# SCH.net
KiCad netlist of a schematic drawn in EasyEDA
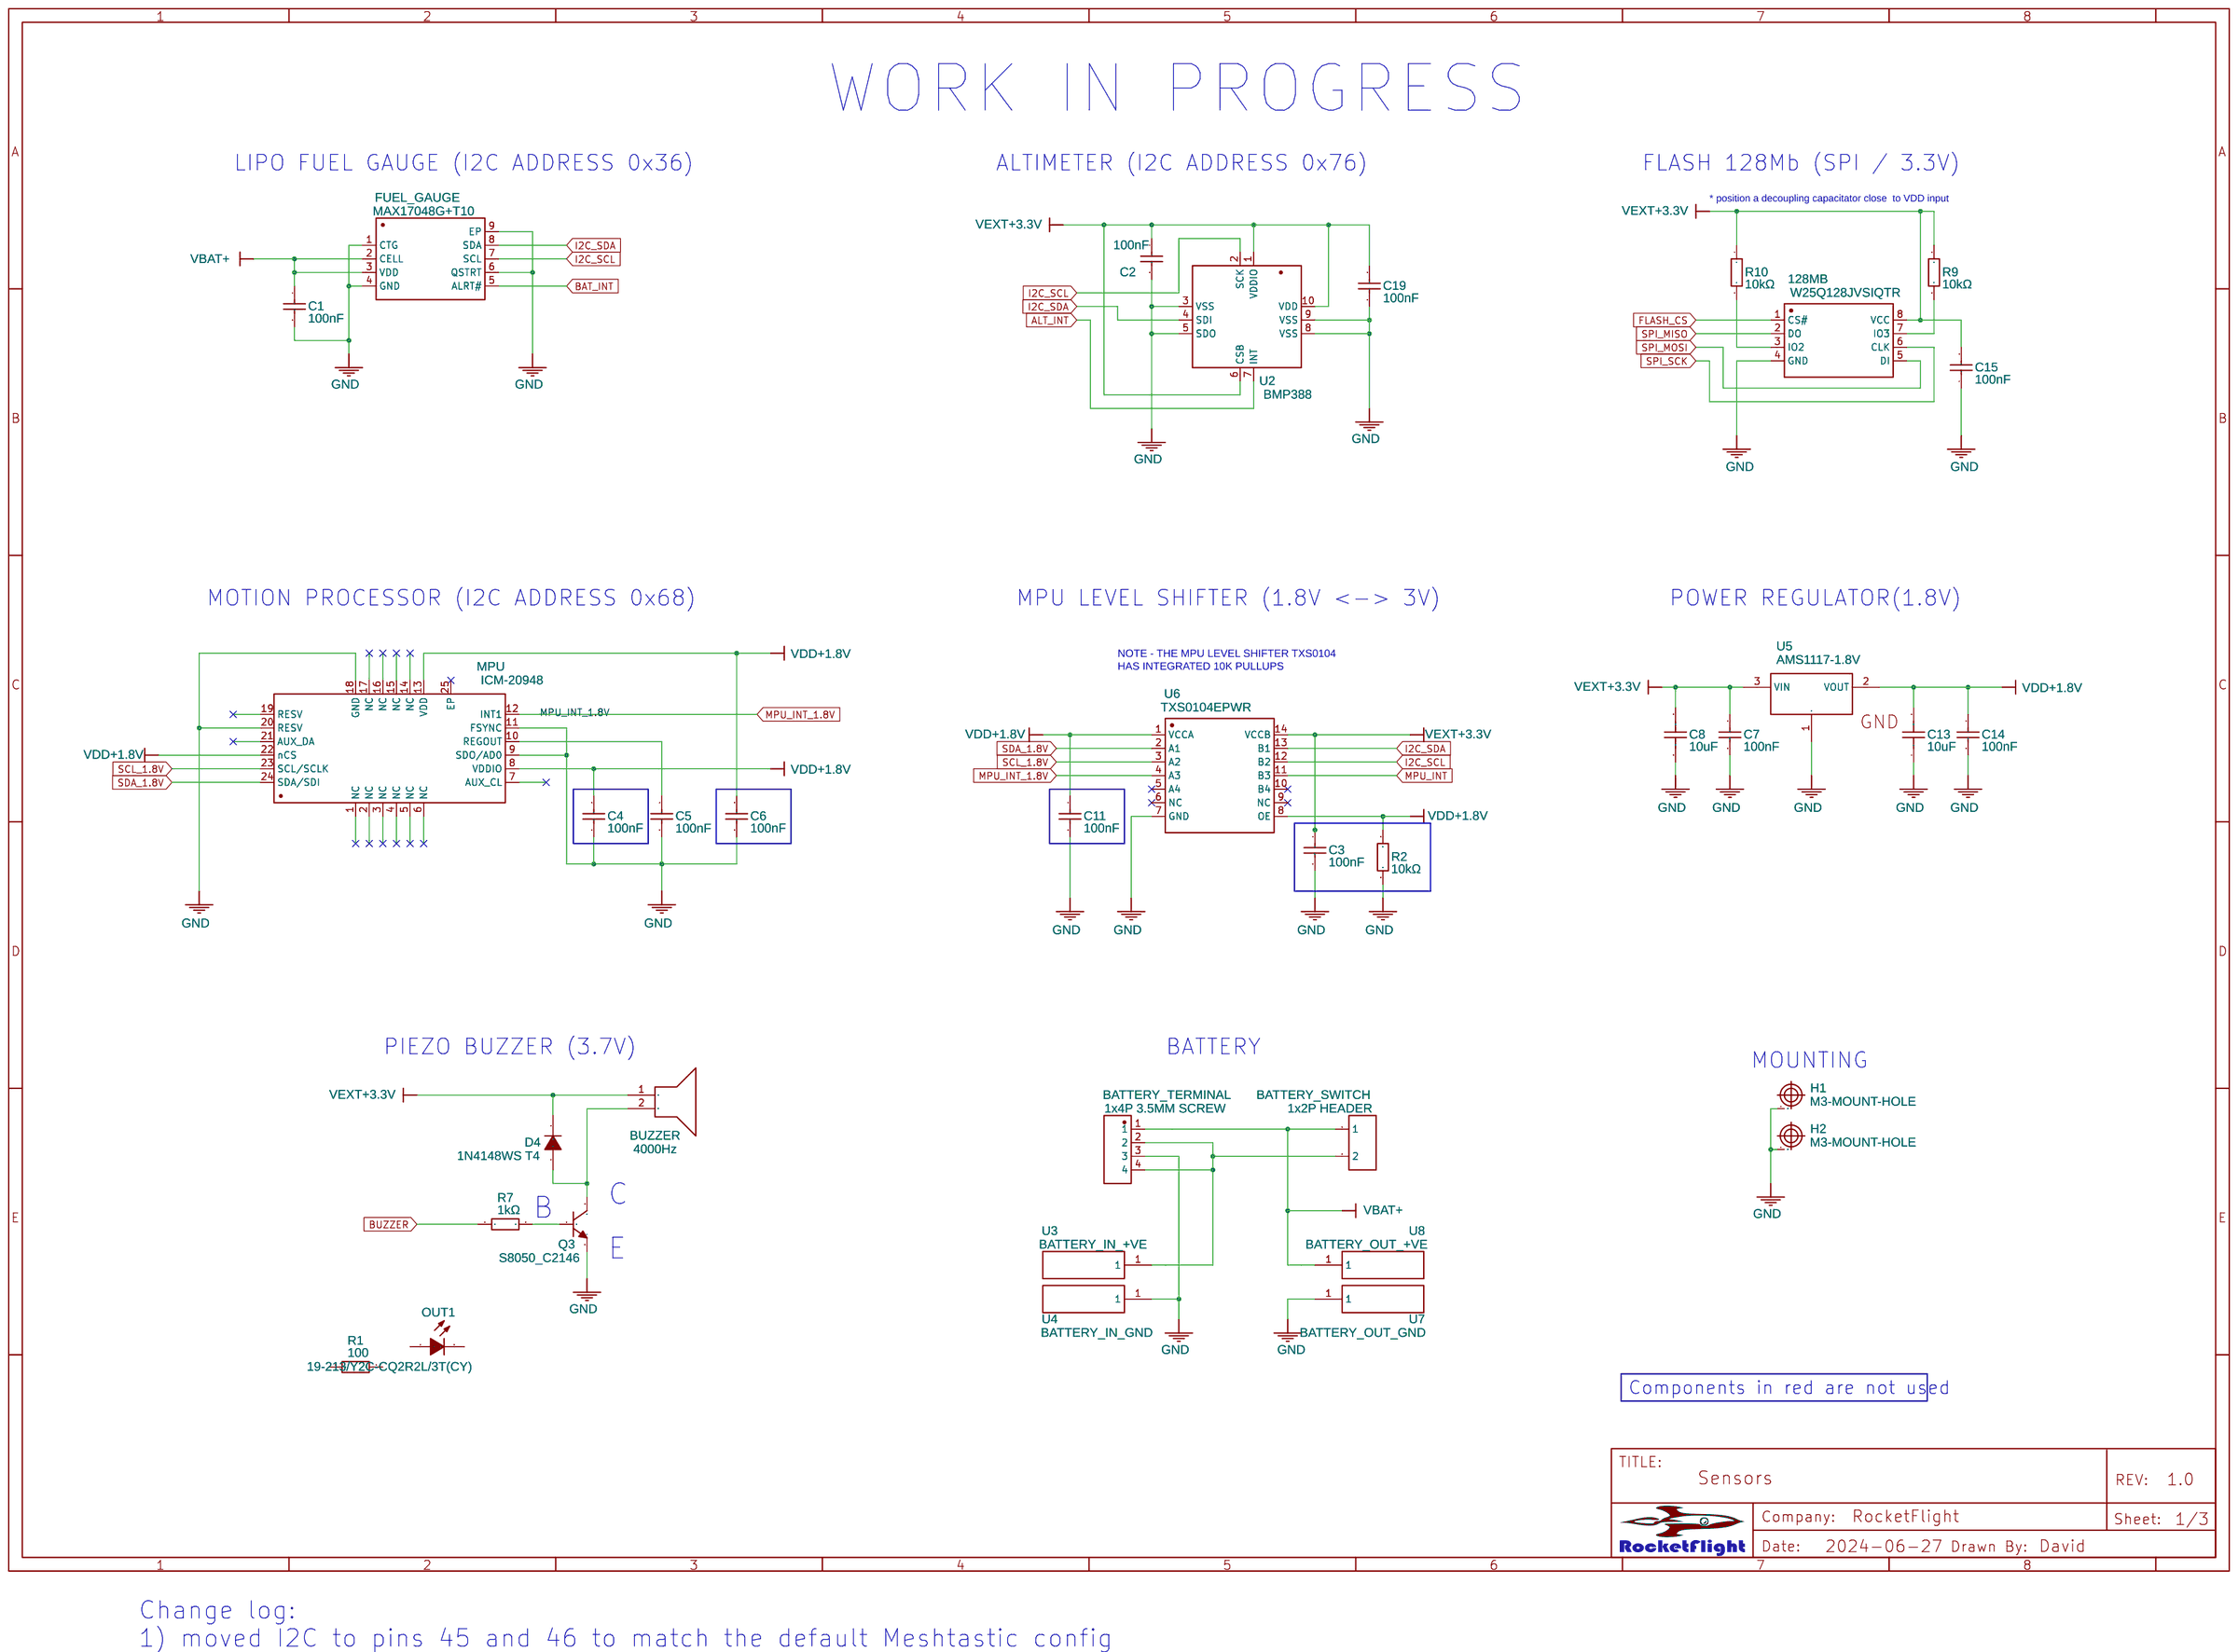
[diagram p0: Sensors]
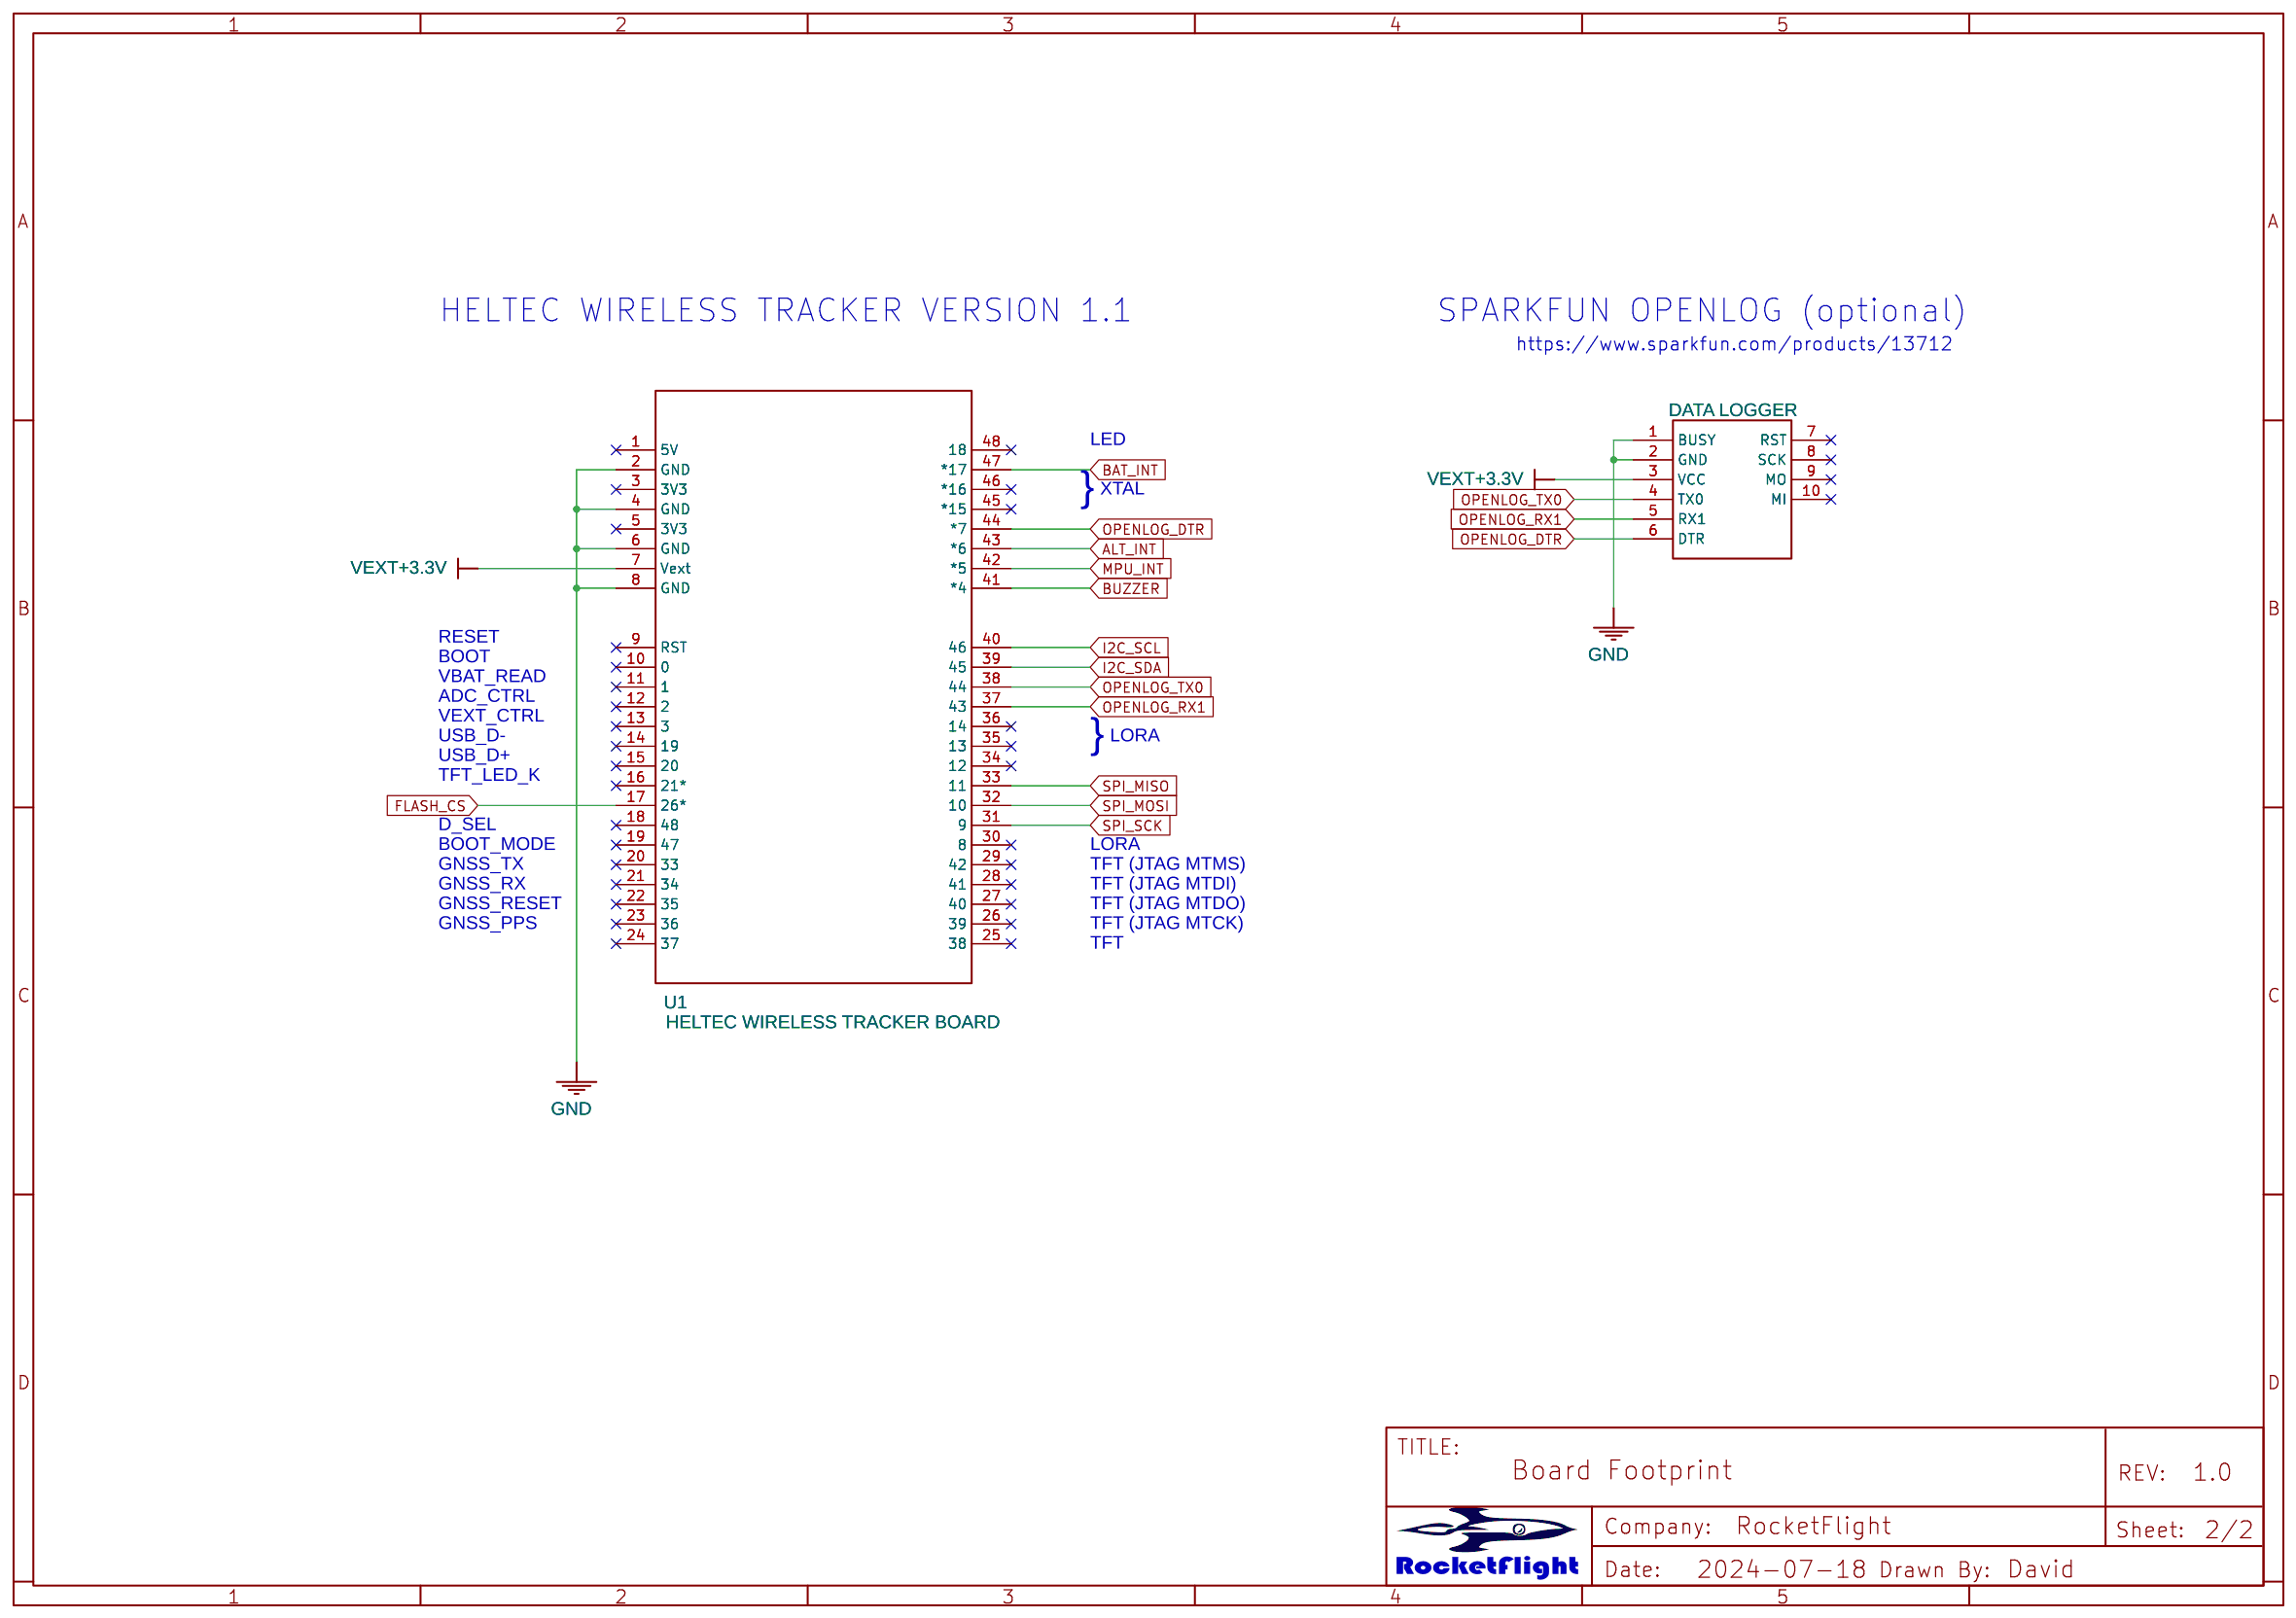
[diagram p1: Board]

(export (version "E")
  (design (tool "Eeschema 10.0.6"))
  (components
    (comp (ref "128MB")
      (value "W25Q128JVSIQTR")
      (fields (field (name "Manufacturer Part") "W25Q128JVSIQ") (field (name "Manufacturer") "WINBOND(华邦)"))
      (libsource (lib "") (part "W25Q128JVSIQTR"))
    )
    (comp (ref "BATTERY_SWITCH")
      (value "1x2P HEADER")
      (fields (field (name "Manufacturer Part") "826629-2") (field (name "Manufacturer") "TE Connectivity"))
      (libsource (lib "") (part "HDR-M-2.54_1X2_ROUND"))
    )
    (comp (ref "BATTERY_TERMINAL")
      (value "1x4P 3.5MM SCREW")
      (fields (field (name "Manufacturer Part") "XY350V-3.5-4P") (field (name "Manufacturer") "--"))
      (libsource (lib "") (part "XY350V-3.5-4P"))
    )
    (comp (ref "BUZZER")
      (value "4000Hz")
      (fields (field (name "Manufacturer Part") "FUET-9018") (field (name "Manufacturer") "FUET(福声科技)"))
      (libsource (lib "") (part "FST-9018 COPY"))
    )
    (comp (ref "C1")
      (value "100nF")
      (fields
        (field (name "Manufacturer Part") "CL05B104KO5NNNC")
        (field (name "Manufacturer") "SAMSUNG(三星)")
      )
      (libsource (lib "") (part "CL05B104KO5NNNC"))
    )
    (comp (ref "C2")
      (value "100nF")
      (fields
        (field (name "Manufacturer Part") "CL05B104KO5NNNC")
        (field (name "Manufacturer") "SAMSUNG(三星)")
      )
      (libsource (lib "") (part "CL05B104KO5NNNC"))
    )
    (comp (ref "C3")
      (value "100nF")
      (fields
        (field (name "Manufacturer Part") "CL05B104KO5NNNC")
        (field (name "Manufacturer") "SAMSUNG(三星)")
      )
      (libsource (lib "") (part "CL05B104KO5NNNC"))
    )
    (comp (ref "C4")
      (value "100nF")
      (fields
        (field (name "Manufacturer Part") "CL05B104KO5NNNC")
        (field (name "Manufacturer") "SAMSUNG(三星)")
      )
      (libsource (lib "") (part "CL05B104KO5NNNC_1"))
    )
    (comp (ref "C5")
      (value "100nF")
      (fields
        (field (name "Manufacturer Part") "CL05B104KO5NNNC")
        (field (name "Manufacturer") "SAMSUNG(三星)")
      )
      (libsource (lib "") (part "CL05B104KO5NNNC"))
    )
    (comp (ref "C6")
      (value "100nF")
      (fields
        (field (name "Manufacturer Part") "CL05B104KO5NNNC")
        (field (name "Manufacturer") "SAMSUNG(三星)")
      )
      (libsource (lib "") (part "CL05B104KO5NNNC_1"))
    )
    (comp (ref "C7")
      (value "100nF")
      (fields
        (field (name "Manufacturer Part") "CL05B104KO5NNNC")
        (field (name "Manufacturer") "SAMSUNG(三星)")
      )
      (libsource (lib "") (part "CL05B104KO5NNNC_1"))
    )
    (comp (ref "C8")
      (value "10uF")
      (fields
        (field (name "Manufacturer Part") "CL10A106MA8NRNC")
        (field (name "Manufacturer") "SAMSUNG(三星)")
      )
      (libsource (lib "") (part "CL10A106MA8NRNC"))
    )
    (comp (ref "C11")
      (value "100nF")
      (fields
        (field (name "Manufacturer Part") "CL05B104KO5NNNC")
        (field (name "Manufacturer") "SAMSUNG(三星)")
      )
      (libsource (lib "") (part "CL05B104KO5NNNC"))
    )
    (comp (ref "C13")
      (value "10uF")
      (fields
        (field (name "Manufacturer Part") "CL10A106MA8NRNC")
        (field (name "Manufacturer") "SAMSUNG(三星)")
      )
      (libsource (lib "") (part "CL10A106MA8NRNC"))
    )
    (comp (ref "C14")
      (value "100nF")
      (fields
        (field (name "Manufacturer Part") "CL05B104KO5NNNC")
        (field (name "Manufacturer") "SAMSUNG(三星)")
      )
      (libsource (lib "") (part "CL05B104KO5NNNC_1"))
    )
    (comp (ref "C15")
      (value "100nF")
      (fields
        (field (name "Manufacturer Part") "CL05B104KO5NNNC")
        (field (name "Manufacturer") "SAMSUNG(三星)")
      )
      (libsource (lib "") (part "CL05B104KO5NNNC_1"))
    )
    (comp (ref "C19")
      (value "100nF")
      (fields
        (field (name "Manufacturer Part") "CL05B104KO5NNNC")
        (field (name "Manufacturer") "SAMSUNG(三星)")
      )
      (libsource (lib "") (part "CL05B104KO5NNNC"))
    )
    (comp (ref "D4")
      (value "1N4148WS T4")
      (fields (field (name "Manufacturer Part") "1N4148WS") (field (name "Manufacturer") "CJ(江苏长电/长晶)"))
      (libsource (lib "") (part "1N4148WS T4"))
    )
    (comp (ref "FUEL_GAUGE")
      (value "MAX17048G+T10")
      (fields (field (name "Manufacturer") "ADI(亚德诺)/MAXIM(美信)"))
      (libsource (lib "") (part "MAX17048G+T10"))
    )
    (comp (ref "H1") (value "M3-MOUNT-HOLE") (libsource (lib "") (part "M3-MOUNT-HOLE")))
    (comp (ref "H2") (value "M3-MOUNT-HOLE") (libsource (lib "") (part "M3-MOUNT-HOLE")))
    (comp (ref "MPU")
      (value "ICM-20948")
      (fields (field (name "Manufacturer") "TDK InvenSense(应美盛)"))
      (libsource (lib "") (part "ICM-20948"))
    )
    (comp (ref "OUT1")
      (value "19-213/Y2C-CQ2R2L/3T(CY)")
      (fields (field (name "Manufacturer") "EVERLIGHT"))
      (libsource (lib "") (part "19-213/Y2C-CQ2R2L/3T(CY)"))
    )
    (comp (ref "Q3")
      (value "S8050_C2146")
      (fields (field (name "Manufacturer Part") "S8050 J3Y") (field (name "Manufacturer") "CJ(江苏长电/长晶)"))
      (libsource (lib "") (part "S8050_C2146"))
    )
    (comp (ref "R1")
      (value "100")
      (fields (field (name "Manufacturer Part") "0603WAF1000T5E") (field (name "Manufacturer") "UniOhm"))
      (libsource (lib "") (part "0603WAF1000T5E"))
    )
    (comp (ref "R2")
      (value "10kΩ")
      (fields
        (field (name "Manufacturer Part") "0402WGF1002TCE")
        (field (name "Manufacturer") "UNI-ROYAL(厚声)")
      )
      (libsource (lib "") (part "0402WGF1002TCE_1"))
    )
    (comp (ref "R7")
      (value "1kΩ")
      (fields
        (field (name "Manufacturer Part") "0603WAF1001T5E")
        (field (name "Manufacturer") "UNI-ROYAL(厚声)")
      )
      (libsource (lib "") (part "0603WAF1001T5E"))
    )
    (comp (ref "R9")
      (value "10kΩ")
      (fields
        (field (name "Manufacturer Part") "0402WGF1002TCE")
        (field (name "Manufacturer") "UNI-ROYAL(厚声)")
      )
      (libsource (lib "") (part "0402WGF1002TCE"))
    )
    (comp (ref "R10")
      (value "10kΩ")
      (fields
        (field (name "Manufacturer Part") "0402WGF1002TCE")
        (field (name "Manufacturer") "UNI-ROYAL(厚声)")
      )
      (libsource (lib "") (part "0402WGF1002TCE"))
    )
    (comp (ref "U2")
      (value "BMP388")
      (fields (field (name "Manufacturer") "Bosch(博世)"))
      (libsource (lib "") (part "BMP388"))
    )
    (comp (ref "U3")
      (value "BATTERY_IN_+VE")
      (fields (field (name "Manufacturer Part") "PAD_5.84mm×1.54mm×0.8mm"))
      (libsource (lib "") (part "MySolderPad1.5x2.5mm"))
    )
    (comp (ref "U4")
      (value "BATTERY_IN_GND")
      (fields (field (name "Manufacturer Part") "PAD_5.84mm×1.54mm×0.8mm"))
      (libsource (lib "") (part "MySolderPad1.5x2.5mm"))
    )
    (comp (ref "U5")
      (value "AMS1117-1.8V")
      (fields (field (name "Manufacturer") "MSKSEMI(美森科)"))
      (libsource (lib "") (part "AMS1117-1.8V"))
    )
    (comp (ref "U6")
      (value "TXS0104EPWR")
      (fields (field (name "Manufacturer") "TI(德州仪器)"))
      (libsource (lib "") (part "TXS0104EPWR"))
    )
    (comp (ref "U7")
      (value "BATTERY_OUT_GND")
      (fields (field (name "Manufacturer Part") "PAD_5.84mm×1.54mm×0.8mm"))
      (libsource (lib "") (part "MySolderPad1.5x2.5mm_1"))
    )
    (comp (ref "U8")
      (value "BATTERY_OUT_+VE")
      (fields (field (name "Manufacturer Part") "PAD_5.84mm×1.54mm×0.8mm"))
      (libsource (lib "") (part "MySolderPad1.5x2.5mm_1"))
    )
    (comp (ref "BUSY")
      (value "DATA LOGGER")
      (fields (field (name "Manufacturer Part") "Sparkfun"))
      (libsource (lib "") (part "DATA LOGGER_RN_OPENLOG COPY"))
    )
    (comp (ref "U1")
      (value "HELTEC WIRELESS TRACKER BOARD")
      (libsource (lib "") (part "HELTEC WIRELESS TRACKER BOARD"))
    )
  )
  (nets
    (net (code "1") (name "ALT_INT") (class "Default")
      (node (ref "U1") (pin "43") (pinfunction "*6_43") (pintype "unspecified"))
      (node (ref "U2") (pin "7") (pinfunction "INT_7") (pintype "unspecified"))
    )
    (net (code "2") (name "BAT_INT") (class "Default")
      (node (ref "FUEL_GAUGE") (pin "5") (pinfunction "ALRT#_5") (pintype "unspecified"))
      (node (ref "U1") (pin "47") (pinfunction "*17_47") (pintype "unspecified"))
    )
    (net (code "3") (name "BUZZER") (class "Default")
      (node (ref "R7") (pin "1") (pinfunction "1_1") (pintype "input"))
      (node (ref "U1") (pin "41") (pinfunction "*4_41") (pintype "unspecified"))
    )
    (net (code "4") (name "FLASH_CS") (class "Default")
      (node (ref "128MB") (pin "1") (pinfunction "CS#_1") (pintype "unspecified"))
      (node (ref "U1") (pin "17") (pinfunction "26*_17") (pintype "unspecified"))
    )
    (net (code "5") (name "GND") (class "Default")
      (node (ref "128MB") (pin "4") (pinfunction "GND_4") (pintype "unspecified"))
      (node (ref "BATTERY_TERMINAL") (pin "3") (pinfunction "3_3") (pintype "unspecified"))
      (node (ref "BUSY") (pin "1") (pinfunction "BUSY_1") (pintype "unspecified"))
      (node (ref "BUSY") (pin "2") (pinfunction "GND_2") (pintype "unspecified"))
      (node (ref "C1") (pin "2") (pinfunction "2_2") (pintype "input"))
      (node (ref "C11") (pin "2") (pinfunction "2_2") (pintype "input"))
      (node (ref "C13") (pin "1") (pinfunction "1_1") (pintype "unspecified"))
      (node (ref "C14") (pin "1") (pinfunction "1_1") (pintype "input"))
      (node (ref "C15") (pin "1") (pinfunction "1_1") (pintype "input"))
      (node (ref "C19") (pin "2") (pinfunction "2_2") (pintype "input"))
      (node (ref "C2") (pin "2") (pinfunction "2_2") (pintype "input"))
      (node (ref "C3") (pin "2") (pinfunction "2_2") (pintype "input"))
      (node (ref "C4") (pin "1") (pinfunction "1_1") (pintype "input"))
      (node (ref "C5") (pin "2") (pinfunction "2_2") (pintype "input"))
      (node (ref "C6") (pin "1") (pinfunction "1_1") (pintype "input"))
      (node (ref "C7") (pin "1") (pinfunction "1_1") (pintype "input"))
      (node (ref "C8") (pin "1") (pinfunction "1_1") (pintype "unspecified"))
      (node (ref "FUEL_GAUGE") (pin "1") (pinfunction "CTG_1") (pintype "unspecified"))
      (node (ref "FUEL_GAUGE") (pin "4") (pinfunction "GND_4") (pintype "unspecified"))
      (node (ref "FUEL_GAUGE") (pin "6") (pinfunction "QSTRT_6") (pintype "unspecified"))
      (node (ref "FUEL_GAUGE") (pin "9") (pinfunction "EP_9") (pintype "unspecified"))
      (node (ref "H1") (pin "1") (pinfunction "GND_1") (pintype "passive"))
      (node (ref "H2") (pin "1") (pinfunction "GND_1") (pintype "passive"))
      (node (ref "MPU") (pin "11") (pinfunction "FSYNC_11") (pintype "unspecified"))
      (node (ref "MPU") (pin "18") (pinfunction "GND_18") (pintype "unspecified"))
      (node (ref "MPU") (pin "20") (pinfunction "RESV_20") (pintype "unspecified"))
      (node (ref "MPU") (pin "9") (pinfunction "SDO/AD0_9") (pintype "unspecified"))
      (node (ref "Q3") (pin "2") (pinfunction "E_2") (pintype "unspecified"))
      (node (ref "R2") (pin "1") (pinfunction "1_1") (pintype "input"))
      (node (ref "U1") (pin "2") (pinfunction "GND_2") (pintype "unspecified"))
      (node (ref "U1") (pin "4") (pinfunction "GND_4") (pintype "unspecified"))
      (node (ref "U1") (pin "6") (pinfunction "GND_6") (pintype "unspecified"))
      (node (ref "U1") (pin "8") (pinfunction "GND_8") (pintype "unspecified"))
      (node (ref "U2") (pin "3") (pinfunction "VSS_3") (pintype "unspecified"))
      (node (ref "U2") (pin "5") (pinfunction "SDO_5") (pintype "unspecified"))
      (node (ref "U2") (pin "8") (pinfunction "VSS_8") (pintype "unspecified"))
      (node (ref "U2") (pin "9") (pinfunction "VSS_9") (pintype "unspecified"))
      (node (ref "U4") (pin "1") (pinfunction "1_1") (pintype "unspecified"))
      (node (ref "U5") (pin "1") (pinfunction "GND_1") (pintype "passive"))
      (node (ref "U6") (pin "7") (pinfunction "GND_7") (pintype "unspecified"))
      (node (ref "U7") (pin "1") (pinfunction "1_1") (pintype "unspecified"))
    )
    (net (code "6") (name "I2C_SCL") (class "Default")
      (node (ref "FUEL_GAUGE") (pin "7") (pinfunction "SCL_7") (pintype "unspecified"))
      (node (ref "U1") (pin "40") (pinfunction "46_40") (pintype "unspecified"))
      (node (ref "U2") (pin "2") (pinfunction "SCK_2") (pintype "unspecified"))
      (node (ref "U6") (pin "12") (pinfunction "B2_12") (pintype "unspecified"))
    )
    (net (code "7") (name "I2C_SDA") (class "Default")
      (node (ref "FUEL_GAUGE") (pin "8") (pinfunction "SDA_8") (pintype "unspecified"))
      (node (ref "U1") (pin "39") (pinfunction "45_39") (pintype "unspecified"))
      (node (ref "U2") (pin "4") (pinfunction "SDI_4") (pintype "unspecified"))
      (node (ref "U6") (pin "13") (pinfunction "B1_13") (pintype "unspecified"))
    )
    (net (code "8") (name "MPU_INT") (class "Default")
      (node (ref "U1") (pin "42") (pinfunction "*5_42") (pintype "unspecified"))
      (node (ref "U6") (pin "11") (pinfunction "B3_11") (pintype "unspecified"))
    )
    (net (code "9") (name "MPU_INT_1.8V") (class "Default")
      (node (ref "MPU") (pin "12") (pinfunction "INT1_12") (pintype "unspecified"))
      (node (ref "U6") (pin "4") (pinfunction "A3_4") (pintype "unspecified"))
    )
    (net (code "10") (name "Net-(128MB-IO2)") (class "Default")
      (node (ref "128MB") (pin "3") (pinfunction "IO2_3") (pintype "unspecified"))
      (node (ref "R10") (pin "2") (pinfunction "2_2") (pintype "input"))
    )
    (net (code "11") (name "Net-(128MB-IO3)") (class "Default")
      (node (ref "128MB") (pin "7") (pinfunction "IO3_7") (pintype "unspecified"))
      (node (ref "R9") (pin "2") (pinfunction "2_2") (pintype "input"))
    )
    (net (code "12") (name "Net-(BATTERY_SWITCH-Pad2)") (class "Default")
      (node (ref "BATTERY_SWITCH") (pin "2") (pinfunction "2_2") (pintype "unspecified"))
      (node (ref "BATTERY_TERMINAL") (pin "2") (pinfunction "2_2") (pintype "unspecified"))
      (node (ref "BATTERY_TERMINAL") (pin "4") (pinfunction "4_4") (pintype "unspecified"))
      (node (ref "U3") (pin "1") (pinfunction "1_1") (pintype "unspecified"))
    )
    (net (code "13") (name "Net-(D4-A)") (class "Default")
      (node (ref "BUZZER") (pin "2") (pinfunction "2_2") (pintype "unspecified"))
      (node (ref "D4") (pin "2") (pinfunction "A_2") (pintype "unspecified"))
      (node (ref "Q3") (pin "3") (pinfunction "C_3") (pintype "unspecified"))
    )
    (net (code "14") (name "Net-(MPU-REGOUT)") (class "Default")
      (node (ref "C5") (pin "1") (pinfunction "1_1") (pintype "input"))
      (node (ref "MPU") (pin "10") (pinfunction "REGOUT_10") (pintype "unspecified"))
    )
    (net (code "15") (name "Net-(Q3-B)") (class "Default")
      (node (ref "Q3") (pin "1") (pinfunction "B_1") (pintype "unspecified"))
      (node (ref "R7") (pin "2") (pinfunction "2_2") (pintype "input"))
    )
    (net (code "16") (name "OPENLOG_DTR") (class "Default")
      (node (ref "BUSY") (pin "6") (pinfunction "DTR_6") (pintype "unspecified"))
      (node (ref "U1") (pin "44") (pinfunction "*7_44") (pintype "unspecified"))
    )
    (net (code "17") (name "OPENLOG_RX1") (class "Default")
      (node (ref "BUSY") (pin "5") (pinfunction "RX1_5") (pintype "unspecified"))
      (node (ref "U1") (pin "37") (pinfunction "43_37") (pintype "unspecified"))
    )
    (net (code "18") (name "OPENLOG_TX0") (class "Default")
      (node (ref "BUSY") (pin "4") (pinfunction "TX0_4") (pintype "unspecified"))
      (node (ref "U1") (pin "38") (pinfunction "44_38") (pintype "unspecified"))
    )
    (net (code "19") (name "SCL_1.8V") (class "Default")
      (node (ref "MPU") (pin "23") (pinfunction "SCL/SCLK_23") (pintype "unspecified"))
      (node (ref "U6") (pin "3") (pinfunction "A2_3") (pintype "unspecified"))
    )
    (net (code "20") (name "SDA_1.8V") (class "Default")
      (node (ref "MPU") (pin "24") (pinfunction "SDA/SDI_24") (pintype "unspecified"))
      (node (ref "U6") (pin "2") (pinfunction "A1_2") (pintype "unspecified"))
    )
    (net (code "21") (name "SPI_MISO") (class "Default")
      (node (ref "128MB") (pin "2") (pinfunction "DO_2") (pintype "unspecified"))
      (node (ref "U1") (pin "33") (pinfunction "11_33") (pintype "unspecified"))
    )
    (net (code "22") (name "SPI_MOSI") (class "Default")
      (node (ref "128MB") (pin "5") (pinfunction "DI_5") (pintype "unspecified"))
      (node (ref "U1") (pin "32") (pinfunction "10_32") (pintype "unspecified"))
    )
    (net (code "23") (name "SPI_SCK") (class "Default")
      (node (ref "128MB") (pin "6") (pinfunction "CLK_6") (pintype "unspecified"))
      (node (ref "U1") (pin "31") (pinfunction "9_31") (pintype "unspecified"))
    )
    (net (code "24") (name "VBAT+") (class "Default")
      (node (ref "BATTERY_SWITCH") (pin "1") (pinfunction "1_1") (pintype "unspecified"))
      (node (ref "BATTERY_TERMINAL") (pin "1") (pinfunction "1_1") (pintype "unspecified"))
      (node (ref "C1") (pin "1") (pinfunction "1_1") (pintype "input"))
      (node (ref "FUEL_GAUGE") (pin "2") (pinfunction "CELL_2") (pintype "unspecified"))
      (node (ref "FUEL_GAUGE") (pin "3") (pinfunction "VDD_3") (pintype "unspecified"))
      (node (ref "U8") (pin "1") (pinfunction "1_1") (pintype "unspecified"))
    )
    (net (code "25") (name "VDD+1.8V") (class "Default")
      (node (ref "C11") (pin "1") (pinfunction "1_1") (pintype "input"))
      (node (ref "C13") (pin "2") (pinfunction "2_2") (pintype "unspecified"))
      (node (ref "C14") (pin "2") (pinfunction "2_2") (pintype "input"))
      (node (ref "C4") (pin "2") (pinfunction "2_2") (pintype "input"))
      (node (ref "C6") (pin "2") (pinfunction "2_2") (pintype "input"))
      (node (ref "MPU") (pin "13") (pinfunction "VDD_13") (pintype "unspecified"))
      (node (ref "MPU") (pin "22") (pinfunction "nCS_22") (pintype "unspecified"))
      (node (ref "MPU") (pin "8") (pinfunction "VDDIO_8") (pintype "unspecified"))
      (node (ref "R2") (pin "2") (pinfunction "2_2") (pintype "input"))
      (node (ref "U5") (pin "2") (pinfunction "VOUT_2") (pintype "passive"))
      (node (ref "U6") (pin "1") (pinfunction "VCCA_1") (pintype "unspecified"))
      (node (ref "U6") (pin "8") (pinfunction "OE_8") (pintype "unspecified"))
    )
    (net (code "26") (name "VEXT+3.3V") (class "Default")
      (node (ref "128MB") (pin "8") (pinfunction "VCC_8") (pintype "unspecified"))
      (node (ref "BUSY") (pin "3") (pinfunction "VCC_3") (pintype "unspecified"))
      (node (ref "BUZZER") (pin "1") (pinfunction "1_1") (pintype "unspecified"))
      (node (ref "C15") (pin "2") (pinfunction "2_2") (pintype "input"))
      (node (ref "C19") (pin "1") (pinfunction "1_1") (pintype "input"))
      (node (ref "C2") (pin "1") (pinfunction "1_1") (pintype "input"))
      (node (ref "C3") (pin "1") (pinfunction "1_1") (pintype "input"))
      (node (ref "C7") (pin "2") (pinfunction "2_2") (pintype "input"))
      (node (ref "C8") (pin "2") (pinfunction "2_2") (pintype "unspecified"))
      (node (ref "D4") (pin "1") (pinfunction "K_1") (pintype "unspecified"))
      (node (ref "R10") (pin "1") (pinfunction "1_1") (pintype "input"))
      (node (ref "R9") (pin "1") (pinfunction "1_1") (pintype "input"))
      (node (ref "U1") (pin "7") (pinfunction "Vext_7") (pintype "unspecified"))
      (node (ref "U2") (pin "1") (pinfunction "VDDIO_1") (pintype "unspecified"))
      (node (ref "U2") (pin "10") (pinfunction "VDD_10") (pintype "unspecified"))
      (node (ref "U2") (pin "6") (pinfunction "CSB_6") (pintype "unspecified"))
      (node (ref "U5") (pin "3") (pinfunction "VIN_3") (pintype "passive"))
      (node (ref "U6") (pin "14") (pinfunction "VCCB_14") (pintype "unspecified"))
    )
    (net (code "27") (name "unconnected-(BUSY-MI-Pad10)") (class "Default")
      (node (ref "BUSY") (pin "10") (pinfunction "MI_10") (pintype "unspecified+no_connect"))
    )
    (net (code "28") (name "unconnected-(BUSY-MO-Pad9)") (class "Default")
      (node (ref "BUSY") (pin "9") (pinfunction "MO_9") (pintype "unspecified+no_connect"))
    )
    (net (code "29") (name "unconnected-(BUSY-RST-Pad7)") (class "Default")
      (node (ref "BUSY") (pin "7") (pinfunction "RST_7") (pintype "unspecified+no_connect"))
    )
    (net (code "30") (name "unconnected-(BUSY-SCK-Pad8)") (class "Default")
      (node (ref "BUSY") (pin "8") (pinfunction "SCK_8") (pintype "unspecified+no_connect"))
    )
    (net (code "31") (name "unconnected-(MPU-AUX_CL-Pad7)") (class "Default")
      (node (ref "MPU") (pin "7") (pinfunction "AUX_CL_7") (pintype "unspecified+no_connect"))
    )
    (net (code "32") (name "unconnected-(MPU-AUX_DA-Pad21)") (class "Default")
      (node (ref "MPU") (pin "21") (pinfunction "AUX_DA_21") (pintype "unspecified+no_connect"))
    )
    (net (code "33") (name "unconnected-(MPU-EP-Pad25)") (class "Default")
      (node (ref "MPU") (pin "25") (pinfunction "EP_25") (pintype "unspecified+no_connect"))
    )
    (net (code "34") (name "unconnected-(MPU-NC-Pad1)") (class "Default")
      (node (ref "MPU") (pin "1") (pinfunction "NC_1") (pintype "unspecified+no_connect"))
    )
    (net (code "35") (name "unconnected-(MPU-NC-Pad2)") (class "Default")
      (node (ref "MPU") (pin "2") (pinfunction "NC_2") (pintype "unspecified+no_connect"))
    )
    (net (code "36") (name "unconnected-(MPU-NC-Pad3)") (class "Default")
      (node (ref "MPU") (pin "3") (pinfunction "NC_3") (pintype "unspecified+no_connect"))
    )
    (net (code "37") (name "unconnected-(MPU-NC-Pad4)") (class "Default")
      (node (ref "MPU") (pin "4") (pinfunction "NC_4") (pintype "unspecified+no_connect"))
    )
    (net (code "38") (name "unconnected-(MPU-NC-Pad5)") (class "Default")
      (node (ref "MPU") (pin "5") (pinfunction "NC_5") (pintype "unspecified+no_connect"))
    )
    (net (code "39") (name "unconnected-(MPU-NC-Pad6)") (class "Default")
      (node (ref "MPU") (pin "6") (pinfunction "NC_6") (pintype "unspecified+no_connect"))
    )
    (net (code "40") (name "unconnected-(MPU-NC-Pad14)") (class "Default")
      (node (ref "MPU") (pin "14") (pinfunction "NC_14") (pintype "unspecified+no_connect"))
    )
    (net (code "41") (name "unconnected-(MPU-NC-Pad15)") (class "Default")
      (node (ref "MPU") (pin "15") (pinfunction "NC_15") (pintype "unspecified+no_connect"))
    )
    (net (code "42") (name "unconnected-(MPU-NC-Pad16)") (class "Default")
      (node (ref "MPU") (pin "16") (pinfunction "NC_16") (pintype "unspecified+no_connect"))
    )
    (net (code "43") (name "unconnected-(MPU-NC-Pad17)") (class "Default")
      (node (ref "MPU") (pin "17") (pinfunction "NC_17") (pintype "unspecified+no_connect"))
    )
    (net (code "44") (name "unconnected-(MPU-RESV-Pad19)") (class "Default")
      (node (ref "MPU") (pin "19") (pinfunction "RESV_19") (pintype "unspecified+no_connect"))
    )
    (net (code "45") (name "unconnected-(OUT1-A-Pad1)") (class "Default")
      (node (ref "OUT1") (pin "1") (pinfunction "A_1") (pintype "input"))
    )
    (net (code "46") (name "unconnected-(OUT1-C-Pad2)") (class "Default")
      (node (ref "OUT1") (pin "2") (pinfunction "C_2") (pintype "input"))
    )
    (net (code "47") (name "unconnected-(R1-Pad1)") (class "Default")
      (node (ref "R1") (pin "1") (pinfunction "1_1") (pintype "input"))
    )
    (net (code "48") (name "unconnected-(R1-Pad2)") (class "Default")
      (node (ref "R1") (pin "2") (pinfunction "2_2") (pintype "input"))
    )
    (net (code "49") (name "unconnected-(U1-*15-Pad45)") (class "Default")
      (node (ref "U1") (pin "45") (pinfunction "*15_45") (pintype "unspecified+no_connect"))
    )
    (net (code "50") (name "unconnected-(U1-*16-Pad46)") (class "Default")
      (node (ref "U1") (pin "46") (pinfunction "*16_46") (pintype "unspecified+no_connect"))
    )
    (net (code "51") (name "unconnected-(U1-0-Pad10)") (class "Default")
      (node (ref "U1") (pin "10") (pinfunction "0_10") (pintype "unspecified+no_connect"))
    )
    (net (code "52") (name "unconnected-(U1-1-Pad11)") (class "Default")
      (node (ref "U1") (pin "11") (pinfunction "1_11") (pintype "unspecified+no_connect"))
    )
    (net (code "53") (name "unconnected-(U1-2-Pad12)") (class "Default")
      (node (ref "U1") (pin "12") (pinfunction "2_12") (pintype "unspecified+no_connect"))
    )
    (net (code "54") (name "unconnected-(U1-3-Pad13)") (class "Default")
      (node (ref "U1") (pin "13") (pinfunction "3_13") (pintype "unspecified+no_connect"))
    )
    (net (code "55") (name "unconnected-(U1-3V3-Pad3)") (class "Default")
      (node (ref "U1") (pin "3") (pinfunction "3V3_3") (pintype "unspecified+no_connect"))
    )
    (net (code "56") (name "unconnected-(U1-3V3-Pad5)") (class "Default")
      (node (ref "U1") (pin "5") (pinfunction "3V3_5") (pintype "unspecified+no_connect"))
    )
    (net (code "57") (name "unconnected-(U1-5V-Pad1)") (class "Default")
      (node (ref "U1") (pin "1") (pinfunction "5V_1") (pintype "unspecified+no_connect"))
    )
    (net (code "58") (name "unconnected-(U1-8-Pad30)") (class "Default")
      (node (ref "U1") (pin "30") (pinfunction "8_30") (pintype "unspecified+no_connect"))
    )
    (net (code "59") (name "unconnected-(U1-12-Pad34)") (class "Default")
      (node (ref "U1") (pin "34") (pinfunction "12_34") (pintype "unspecified+no_connect"))
    )
    (net (code "60") (name "unconnected-(U1-13-Pad35)") (class "Default")
      (node (ref "U1") (pin "35") (pinfunction "13_35") (pintype "unspecified+no_connect"))
    )
    (net (code "61") (name "unconnected-(U1-14-Pad36)") (class "Default")
      (node (ref "U1") (pin "36") (pinfunction "14_36") (pintype "unspecified+no_connect"))
    )
    (net (code "62") (name "unconnected-(U1-18-Pad48)") (class "Default")
      (node (ref "U1") (pin "48") (pinfunction "18_48") (pintype "unspecified+no_connect"))
    )
    (net (code "63") (name "unconnected-(U1-19-Pad14)") (class "Default")
      (node (ref "U1") (pin "14") (pinfunction "19_14") (pintype "unspecified+no_connect"))
    )
    (net (code "64") (name "unconnected-(U1-20-Pad15)") (class "Default")
      (node (ref "U1") (pin "15") (pinfunction "20_15") (pintype "unspecified+no_connect"))
    )
    (net (code "65") (name "unconnected-(U1-21*-Pad16)") (class "Default")
      (node (ref "U1") (pin "16") (pinfunction "21*_16") (pintype "unspecified+no_connect"))
    )
    (net (code "66") (name "unconnected-(U1-33-Pad20)") (class "Default")
      (node (ref "U1") (pin "20") (pinfunction "33_20") (pintype "unspecified+no_connect"))
    )
    (net (code "67") (name "unconnected-(U1-34-Pad21)") (class "Default")
      (node (ref "U1") (pin "21") (pinfunction "34_21") (pintype "unspecified+no_connect"))
    )
    (net (code "68") (name "unconnected-(U1-35-Pad22)") (class "Default")
      (node (ref "U1") (pin "22") (pinfunction "35_22") (pintype "unspecified+no_connect"))
    )
    (net (code "69") (name "unconnected-(U1-36-Pad23)") (class "Default")
      (node (ref "U1") (pin "23") (pinfunction "36_23") (pintype "unspecified+no_connect"))
    )
    (net (code "70") (name "unconnected-(U1-37-Pad24)") (class "Default")
      (node (ref "U1") (pin "24") (pinfunction "37_24") (pintype "unspecified+no_connect"))
    )
    (net (code "71") (name "unconnected-(U1-38-Pad25)") (class "Default")
      (node (ref "U1") (pin "25") (pinfunction "38_25") (pintype "unspecified+no_connect"))
    )
    (net (code "72") (name "unconnected-(U1-39-Pad26)") (class "Default")
      (node (ref "U1") (pin "26") (pinfunction "39_26") (pintype "unspecified+no_connect"))
    )
    (net (code "73") (name "unconnected-(U1-40-Pad27)") (class "Default")
      (node (ref "U1") (pin "27") (pinfunction "40_27") (pintype "unspecified+no_connect"))
    )
    (net (code "74") (name "unconnected-(U1-41-Pad28)") (class "Default")
      (node (ref "U1") (pin "28") (pinfunction "41_28") (pintype "unspecified+no_connect"))
    )
    (net (code "75") (name "unconnected-(U1-42-Pad29)") (class "Default")
      (node (ref "U1") (pin "29") (pinfunction "42_29") (pintype "unspecified+no_connect"))
    )
    (net (code "76") (name "unconnected-(U1-47-Pad19)") (class "Default")
      (node (ref "U1") (pin "19") (pinfunction "47_19") (pintype "unspecified+no_connect"))
    )
    (net (code "77") (name "unconnected-(U1-48-Pad18)") (class "Default")
      (node (ref "U1") (pin "18") (pinfunction "48_18") (pintype "unspecified+no_connect"))
    )
    (net (code "78") (name "unconnected-(U1-RST-Pad9)") (class "Default")
      (node (ref "U1") (pin "9") (pinfunction "RST_9") (pintype "unspecified+no_connect"))
    )
    (net (code "79") (name "unconnected-(U6-A4-Pad5)") (class "Default")
      (node (ref "U6") (pin "5") (pinfunction "A4_5") (pintype "unspecified+no_connect"))
    )
    (net (code "80") (name "unconnected-(U6-B4-Pad10)") (class "Default")
      (node (ref "U6") (pin "10") (pinfunction "B4_10") (pintype "unspecified+no_connect"))
    )
    (net (code "81") (name "unconnected-(U6-NC-Pad6)") (class "Default")
      (node (ref "U6") (pin "6") (pinfunction "NC_6") (pintype "unspecified+no_connect"))
    )
    (net (code "82") (name "unconnected-(U6-NC-Pad9)") (class "Default")
      (node (ref "U6") (pin "9") (pinfunction "NC_9") (pintype "unspecified+no_connect"))
    )
  )
)
